# Control_HAT_v0_3A.net
KiCad netlist of a schematic drawn in EAGLE
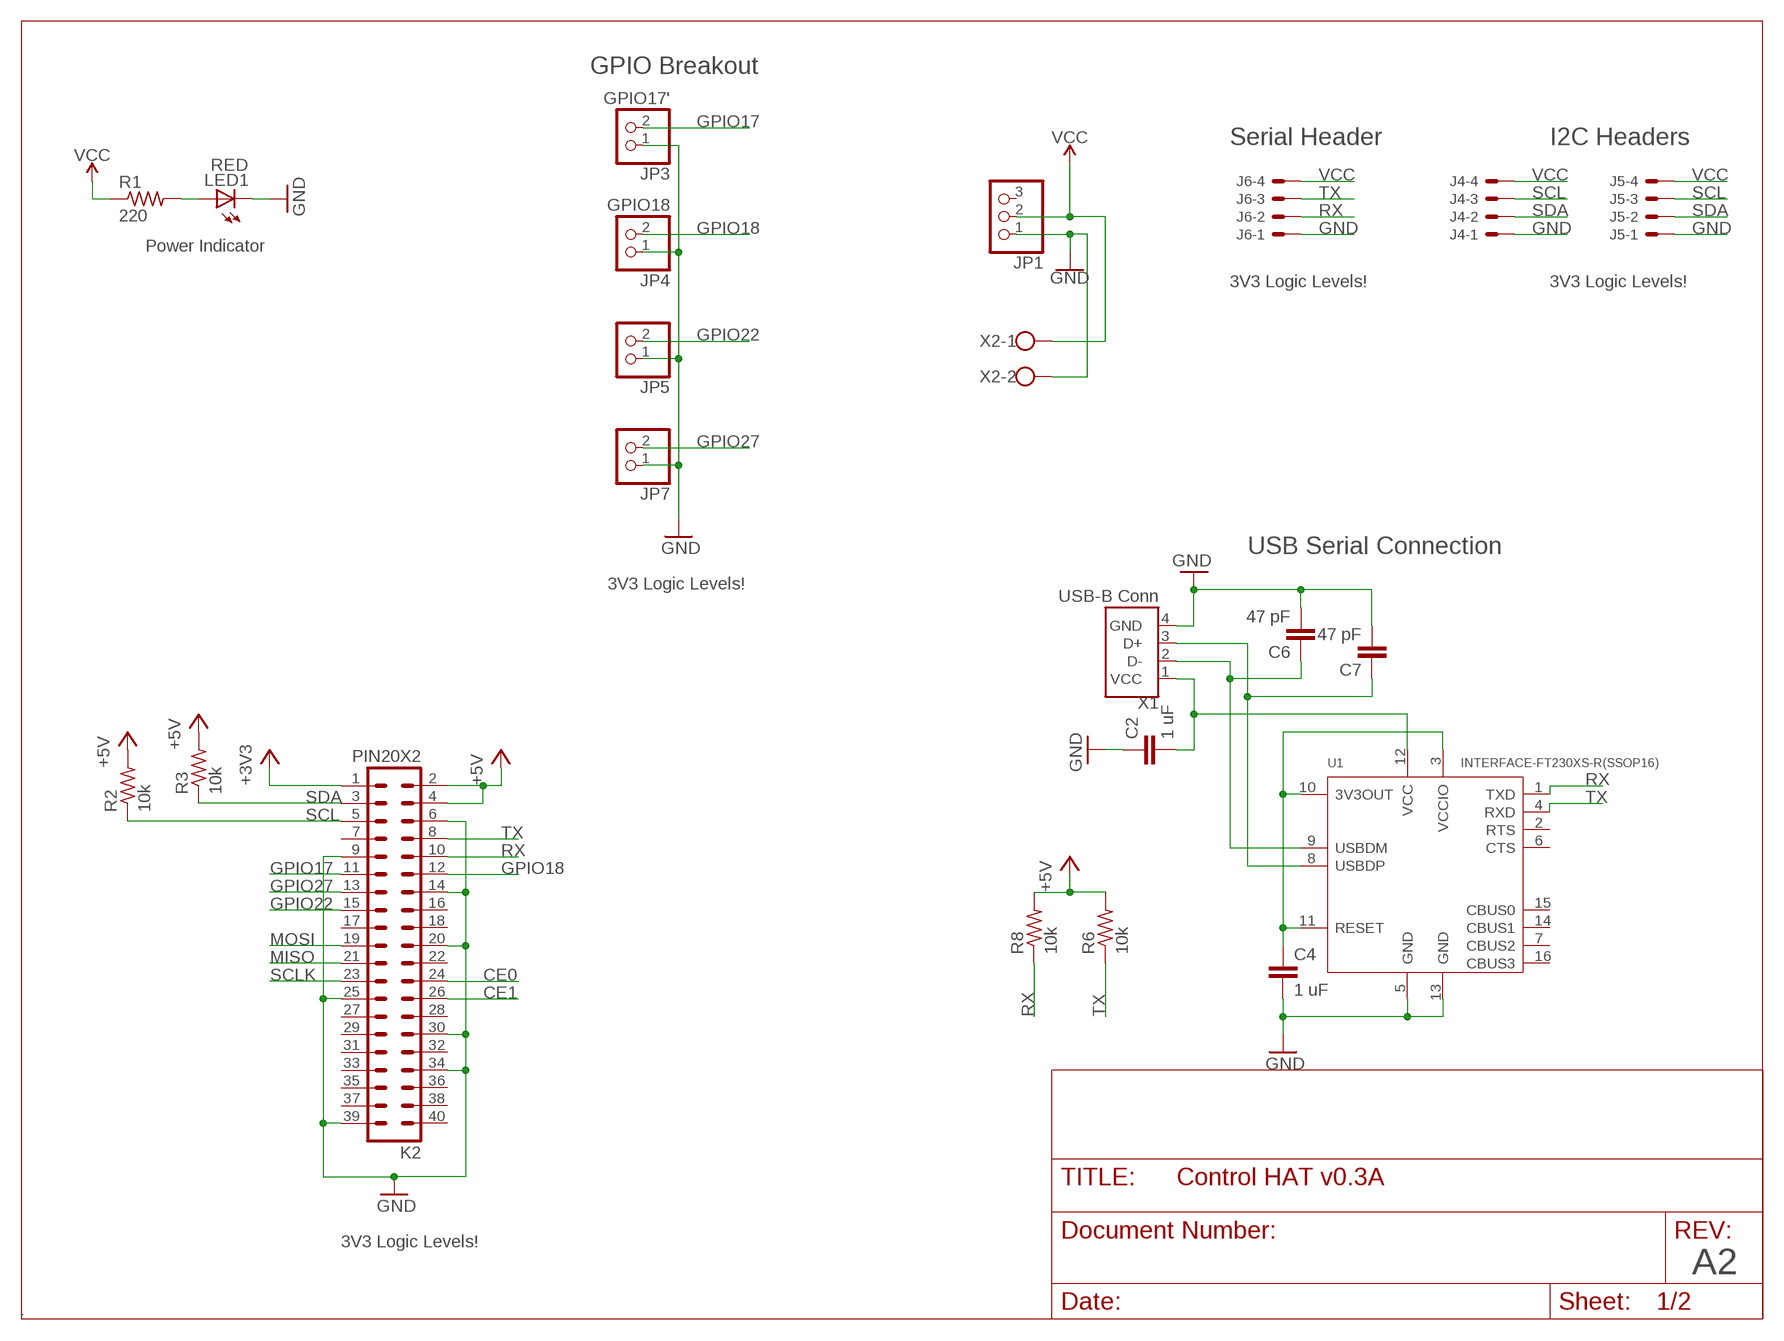
[diagram p0: schematic, sheet 1]
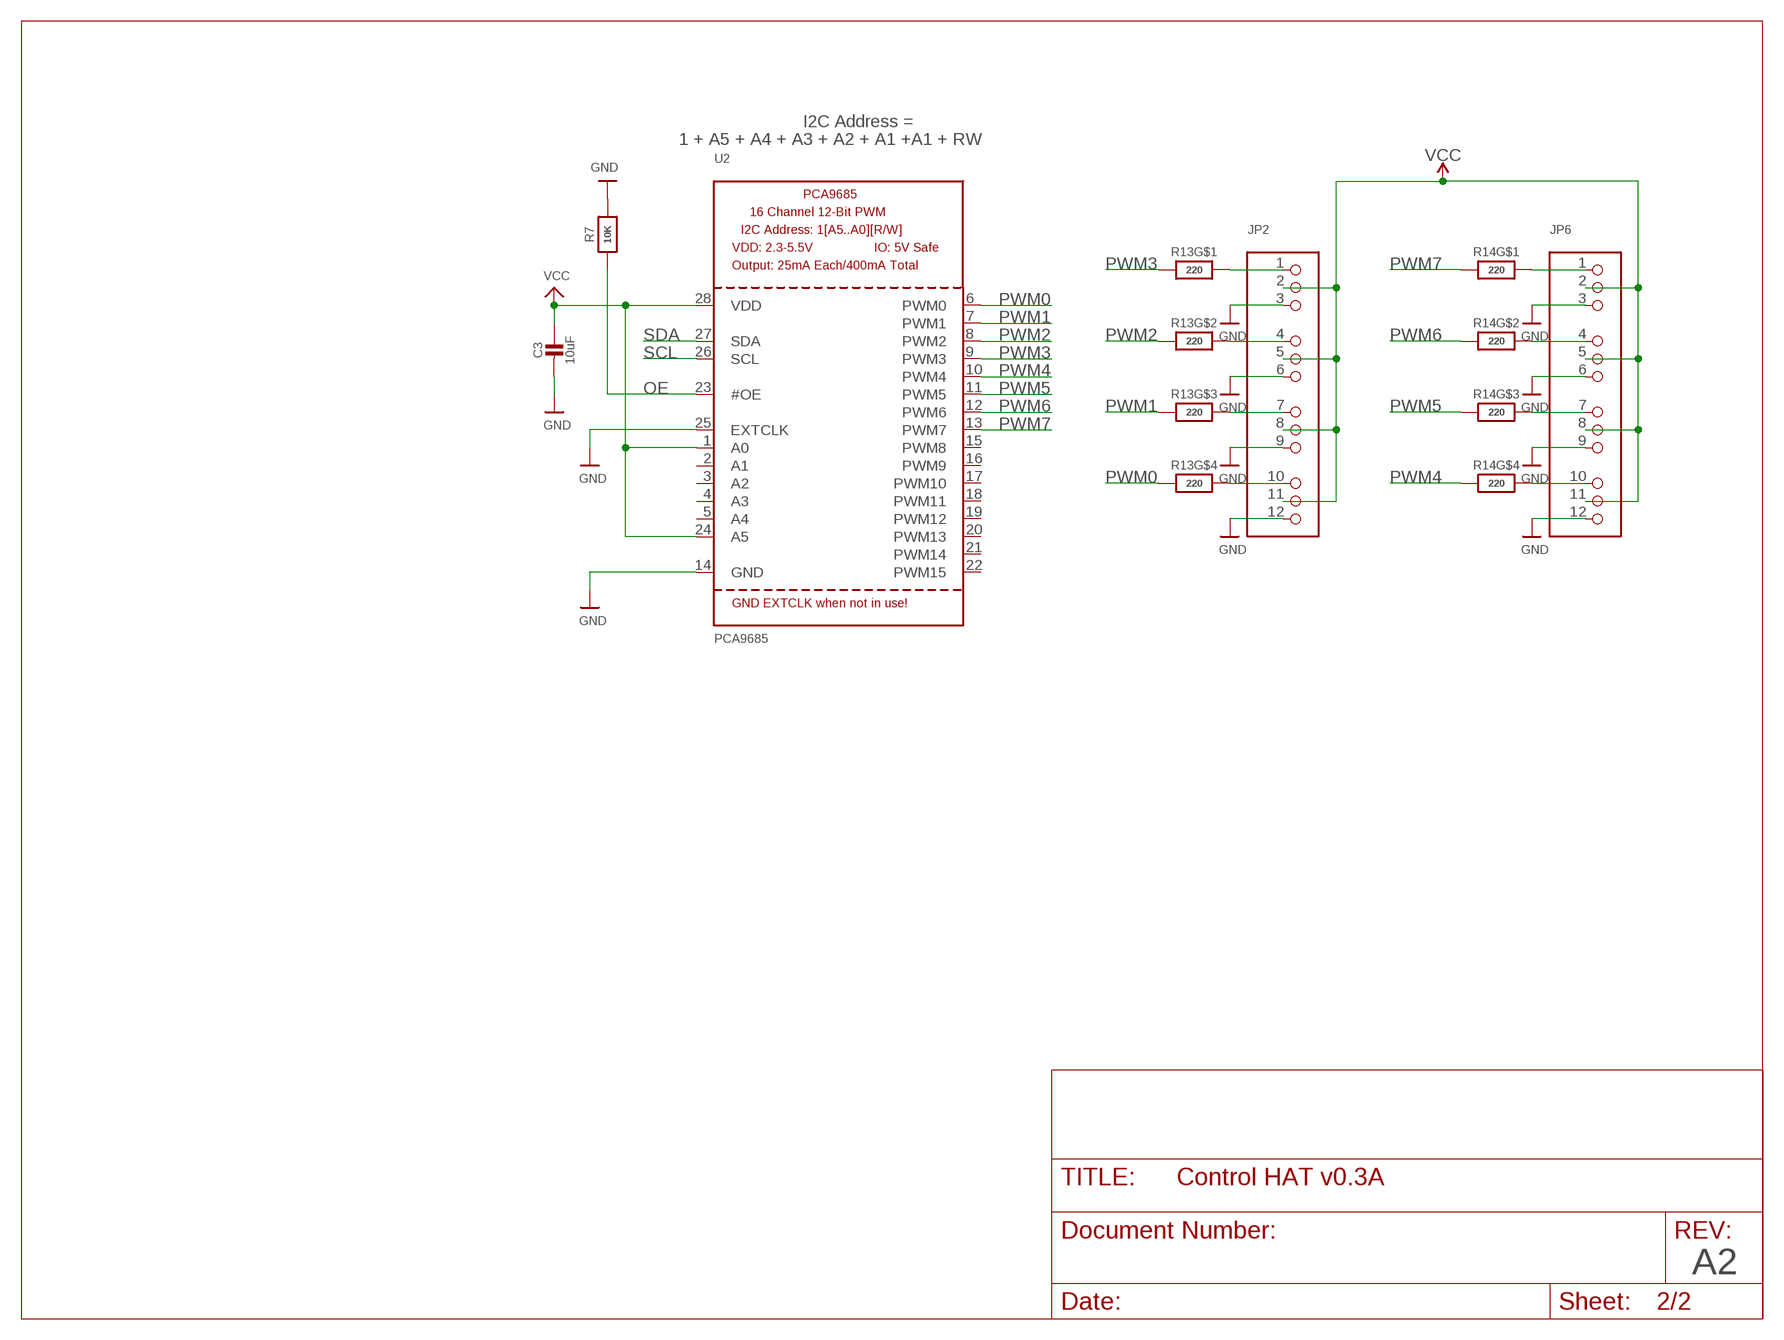
[diagram p1: schematic, sheet 2]

(export (version "E")
  (design (tool "Eeschema 10.0.6"))
  (components
    (comp (ref "C3")
      (value "10uF")
      (footprint "eagle-import:0805-NO")
      (libsource (lib "eagle-import") (part "CAP_CERAMIC0805-NOOUTLINE"))
    )
    (comp (ref "JP2")
      (value "HEADER-3X04")
      (footprint "eagle-import:3X04")
      (libsource (lib "eagle-import") (part "HEADER-3X04"))
    )
    (comp (ref "JP6")
      (value "HEADER-3X04")
      (footprint "eagle-import:3X04")
      (libsource (lib "eagle-import") (part "HEADER-3X04"))
    )
    (comp (ref "R7")
      (value "10K")
      (footprint "eagle-import:0805-NO")
      (libsource (lib "eagle-import") (part "RESISTOR0805_NOOUTLINE"))
    )
    (comp (ref "R13")
      (value "220")
      (footprint "eagle-import:RESPACK_4X0603")
      (libsource (lib "eagle-import") (part "RESISTOR_4PACK"))
    )
    (comp (ref "R14")
      (value "220")
      (footprint "eagle-import:RESPACK_4X0603")
      (libsource (lib "eagle-import") (part "RESISTOR_4PACK"))
    )
    (comp (ref "U2")
      (value "PCA9685")
      (footprint "eagle-import:TSSOP28")
      (libsource (lib "eagle-import") (part "PCA9685"))
    )
    (comp (ref "C2")
      (value "1 uF")
      (footprint "eagle-import:C0603")
      (libsource (lib "eagle-import") (part "C-EUC0603"))
    )
    (comp (ref "C4")
      (value "1 uF")
      (footprint "eagle-import:C0603")
      (libsource (lib "eagle-import") (part "C-EUC0603"))
    )
    (comp (ref "C6")
      (value "47 pF")
      (footprint "eagle-import:C0603")
      (libsource (lib "eagle-import") (part "C-EUC0603"))
    )
    (comp (ref "C7")
      (value "47 pF")
      (footprint "eagle-import:C0603")
      (libsource (lib "eagle-import") (part "C-EUC0603"))
    )
    (comp (ref "J4")
      (value "JST-XH-04-PIN-LONG-PAD")
      (footprint "eagle-import:JST-XH-04-PACKAGE-LONG-PAD")
      (libsource (lib "eagle-import") (part "JST-XH-04-PIN-LONG-PAD"))
    )
    (comp (ref "J5")
      (value "JST-XH-04-PIN-LONG-PAD")
      (footprint "eagle-import:JST-XH-04-PACKAGE-LONG-PAD")
      (libsource (lib "eagle-import") (part "JST-XH-04-PIN-LONG-PAD"))
    )
    (comp (ref "J6")
      (value "JST-XH-04-PIN-LONG-PAD")
      (footprint "eagle-import:JST-XH-04-PACKAGE-LONG-PAD")
      (libsource (lib "eagle-import") (part "JST-XH-04-PIN-LONG-PAD"))
    )
    (comp (ref "JP1")
      (value "PINHD-1X3")
      (footprint "eagle-import:1X03")
      (libsource (lib "eagle-import") (part "PINHD-1X3"))
    )
    (comp (ref "JP3")
      (value "GPIO17'")
      (footprint "eagle-import:1X02")
      (libsource (lib "eagle-import") (part "PINHD-1X2"))
    )
    (comp (ref "JP4")
      (value "GPIO18")
      (footprint "eagle-import:1X02")
      (libsource (lib "eagle-import") (part "PINHD-1X2"))
    )
    (comp (ref "JP5")
      (value "PINHD-1X2")
      (footprint "eagle-import:1X02")
      (libsource (lib "eagle-import") (part "PINHD-1X2"))
    )
    (comp (ref "JP7")
      (value "PINHD-1X2")
      (footprint "eagle-import:1X02")
      (libsource (lib "eagle-import") (part "PINHD-1X2"))
    )
    (comp (ref "K2")
      (value "PIN20X2")
      (footprint "eagle-import:PIN_20X2")
      (libsource (lib "eagle-import") (part "PIN20X2"))
    )
    (comp (ref "LED1")
      (value "RED")
      (footprint "eagle-import:CHIP-LED0603")
      (libsource (lib "eagle-import") (part "LEDCHIP-LED0603"))
    )
    (comp (ref "R1")
      (value "220")
      (footprint "eagle-import:M1206")
      (libsource (lib "eagle-import") (part "R-US_M1206"))
    )
    (comp (ref "R2")
      (value "10k")
      (footprint "eagle-import:M1206")
      (libsource (lib "eagle-import") (part "R-US_M1206"))
    )
    (comp (ref "R3")
      (value "10k")
      (footprint "eagle-import:M1206")
      (libsource (lib "eagle-import") (part "R-US_M1206"))
    )
    (comp (ref "R6")
      (value "10k")
      (footprint "eagle-import:M1206")
      (libsource (lib "eagle-import") (part "R-US_M1206"))
    )
    (comp (ref "R8")
      (value "10k")
      (footprint "eagle-import:M1206")
      (libsource (lib "eagle-import") (part "R-US_M1206"))
    )
    (comp (ref "U1")
      (value "INTERFACE-FT230XS-R(SSOP16)")
      (footprint "eagle-import:SSOP16-0.635-5X4MM")
      (fields (field (name "MF") "FTDI,") (field (name "MP") "FT230XS-R"))
      (libsource (lib "eagle-import") (part "INTERFACE-FT230XS-R(SSOP16)"))
    )
    (comp (ref "X1")
      (value "USB-B Conn")
      (footprint "eagle-import:OST_USB-B1HSB6")
      (fields (field (name "MF") "On Shore") (field (name "MP") "USB-B1HSB6"))
      (libsource (lib "eagle-import") (part "USB-B1HSB6"))
    )
    (comp (ref "X2")
      (value "W237-102")
      (footprint "eagle-import:W237-102")
      (fields (field (name "MPN") "237-102"))
      (libsource (lib "eagle-import") (part "W237-102"))
    )
  )
  (nets
    (net (code "1") (name "+3V3") (class "Default")
      (node (ref "K2") (pin "1") (pinfunction "1_1") (pintype "passive"))
    )
    (net (code "2") (name "+5V") (class "Default")
      (node (ref "K2") (pin "2") (pinfunction "2_2") (pintype "passive"))
      (node (ref "K2") (pin "4") (pinfunction "4_4") (pintype "passive"))
      (node (ref "R2") (pin "2") (pinfunction "2_2") (pintype "passive"))
      (node (ref "R3") (pin "2") (pinfunction "2_2") (pintype "passive"))
      (node (ref "R6") (pin "2") (pinfunction "2_2") (pintype "passive"))
      (node (ref "R8") (pin "2") (pinfunction "2_2") (pintype "passive"))
    )
    (net (code "3") (name "CE0") (class "Default")
      (node (ref "K2") (pin "24") (pinfunction "24_24") (pintype "passive"))
    )
    (net (code "4") (name "CE1") (class "Default")
      (node (ref "K2") (pin "26") (pinfunction "26_26") (pintype "passive"))
    )
    (net (code "5") (name "GND") (class "Default")
      (node (ref "C2") (pin "1") (pinfunction "1_1") (pintype "passive"))
      (node (ref "C3") (pin "2") (pinfunction "2_2") (pintype "passive"))
      (node (ref "C4") (pin "2") (pinfunction "2_2") (pintype "passive"))
      (node (ref "C6") (pin "2") (pinfunction "2_2") (pintype "passive"))
      (node (ref "C7") (pin "2") (pinfunction "2_2") (pintype "passive"))
      (node (ref "J4") (pin "1") (pinfunction "S_1") (pintype "passive"))
      (node (ref "J5") (pin "1") (pinfunction "S_1") (pintype "passive"))
      (node (ref "J6") (pin "1") (pinfunction "S_1") (pintype "passive"))
      (node (ref "JP1") (pin "1") (pinfunction "1_1") (pintype "passive"))
      (node (ref "JP2") (pin "12") (pinfunction "12_12") (pintype "passive"))
      (node (ref "JP2") (pin "3") (pinfunction "3_3") (pintype "passive"))
      (node (ref "JP2") (pin "6") (pinfunction "6_6") (pintype "passive"))
      (node (ref "JP2") (pin "9") (pinfunction "9_9") (pintype "passive"))
      (node (ref "JP3") (pin "1") (pinfunction "1_1") (pintype "passive"))
      (node (ref "JP4") (pin "1") (pinfunction "1_1") (pintype "passive"))
      (node (ref "JP5") (pin "1") (pinfunction "1_1") (pintype "passive"))
      (node (ref "JP6") (pin "12") (pinfunction "12_12") (pintype "passive"))
      (node (ref "JP6") (pin "3") (pinfunction "3_3") (pintype "passive"))
      (node (ref "JP6") (pin "6") (pinfunction "6_6") (pintype "passive"))
      (node (ref "JP6") (pin "9") (pinfunction "9_9") (pintype "passive"))
      (node (ref "JP7") (pin "1") (pinfunction "1_1") (pintype "passive"))
      (node (ref "K2") (pin "14") (pinfunction "14_14") (pintype "passive"))
      (node (ref "K2") (pin "20") (pinfunction "20_20") (pintype "passive"))
      (node (ref "K2") (pin "25") (pinfunction "25_25") (pintype "passive"))
      (node (ref "K2") (pin "30") (pinfunction "30_30") (pintype "passive"))
      (node (ref "K2") (pin "34") (pinfunction "34_34") (pintype "passive"))
      (node (ref "K2") (pin "39") (pinfunction "39_39") (pintype "passive"))
      (node (ref "K2") (pin "6") (pinfunction "6_6") (pintype "passive"))
      (node (ref "K2") (pin "9") (pinfunction "9_9") (pintype "passive"))
      (node (ref "LED1") (pin "C") (pinfunction "C_C") (pintype "passive"))
      (node (ref "R7") (pin "2") (pinfunction "2_2") (pintype "passive"))
      (node (ref "U1") (pin "13") (pinfunction "GND_13") (pintype "bidirectional"))
      (node (ref "U1") (pin "5") (pinfunction "GND_5") (pintype "bidirectional"))
      (node (ref "U2") (pin "14") (pinfunction "GND_14") (pintype "power_in"))
      (node (ref "U2") (pin "25") (pinfunction "EXTCLK_25") (pintype "input"))
      (node (ref "X1") (pin "4") (pinfunction "GND_4") (pintype "power_in"))
      (node (ref "X2") (pin "2") (pinfunction "KL_2") (pintype "passive"))
    )
    (net (code "6") (name "GPIO17") (class "Default")
      (node (ref "JP3") (pin "2") (pinfunction "2_2") (pintype "passive"))
      (node (ref "K2") (pin "11") (pinfunction "11_11") (pintype "passive"))
    )
    (net (code "7") (name "GPIO18") (class "Default")
      (node (ref "JP4") (pin "2") (pinfunction "2_2") (pintype "passive"))
      (node (ref "K2") (pin "12") (pinfunction "12_12") (pintype "passive"))
    )
    (net (code "8") (name "GPIO22") (class "Default")
      (node (ref "JP5") (pin "2") (pinfunction "2_2") (pintype "passive"))
      (node (ref "K2") (pin "15") (pinfunction "15_15") (pintype "passive"))
    )
    (net (code "9") (name "GPIO27") (class "Default")
      (node (ref "JP7") (pin "2") (pinfunction "2_2") (pintype "passive"))
      (node (ref "K2") (pin "13") (pinfunction "13_13") (pintype "passive"))
    )
    (net (code "10") (name "MISO") (class "Default")
      (node (ref "K2") (pin "21") (pinfunction "21_21") (pintype "passive"))
    )
    (net (code "11") (name "MOSI") (class "Default")
      (node (ref "K2") (pin "19") (pinfunction "19_19") (pintype "passive"))
    )
    (net (code "12") (name "Net-(LED1-PadA)") (class "Default")
      (node (ref "LED1") (pin "A") (pinfunction "A_A") (pintype "passive"))
      (node (ref "R1") (pin "2") (pinfunction "2_2") (pintype "passive"))
    )
    (net (code "13") (name "Net-(R13A-2)") (class "Default")
      (node (ref "JP2") (pin "1") (pinfunction "1_1") (pintype "passive"))
      (node (ref "R13") (pin "8") (pinfunction "2_8") (pintype "passive"))
    )
    (net (code "14") (name "Net-(R13B-2)") (class "Default")
      (node (ref "JP2") (pin "4") (pinfunction "4_4") (pintype "passive"))
      (node (ref "R13") (pin "7") (pinfunction "2_7") (pintype "passive"))
    )
    (net (code "15") (name "Net-(R13C-2)") (class "Default")
      (node (ref "JP2") (pin "7") (pinfunction "7_7") (pintype "passive"))
      (node (ref "R13") (pin "6") (pinfunction "2_6") (pintype "passive"))
    )
    (net (code "16") (name "Net-(R13D-2)") (class "Default")
      (node (ref "JP2") (pin "10") (pinfunction "10_10") (pintype "passive"))
      (node (ref "R13") (pin "5") (pinfunction "2_5") (pintype "passive"))
    )
    (net (code "17") (name "Net-(R14A-2)") (class "Default")
      (node (ref "JP6") (pin "1") (pinfunction "1_1") (pintype "passive"))
      (node (ref "R14") (pin "8") (pinfunction "2_8") (pintype "passive"))
    )
    (net (code "18") (name "Net-(R14B-2)") (class "Default")
      (node (ref "JP6") (pin "4") (pinfunction "4_4") (pintype "passive"))
      (node (ref "R14") (pin "7") (pinfunction "2_7") (pintype "passive"))
    )
    (net (code "19") (name "Net-(R14C-2)") (class "Default")
      (node (ref "JP6") (pin "7") (pinfunction "7_7") (pintype "passive"))
      (node (ref "R14") (pin "6") (pinfunction "2_6") (pintype "passive"))
    )
    (net (code "20") (name "Net-(R14D-2)") (class "Default")
      (node (ref "JP6") (pin "10") (pinfunction "10_10") (pintype "passive"))
      (node (ref "R14") (pin "5") (pinfunction "2_5") (pintype "passive"))
    )
    (net (code "21") (name "Net-(U1-3V3OUT)") (class "Default")
      (node (ref "C4") (pin "1") (pinfunction "1_1") (pintype "passive"))
      (node (ref "U1") (pin "10") (pinfunction "3V3OUT_10") (pintype "bidirectional"))
      (node (ref "U1") (pin "11") (pinfunction "RESET_11") (pintype "bidirectional"))
      (node (ref "U1") (pin "3") (pinfunction "VCCIO_3") (pintype "bidirectional"))
    )
    (net (code "22") (name "Net-(U1-USBDM)") (class "Default")
      (node (ref "C6") (pin "1") (pinfunction "1_1") (pintype "passive"))
      (node (ref "U1") (pin "9") (pinfunction "USBDM_9") (pintype "bidirectional"))
      (node (ref "X1") (pin "2") (pinfunction "D-_2") (pintype "bidirectional"))
    )
    (net (code "23") (name "Net-(U1-USBDP)") (class "Default")
      (node (ref "C7") (pin "1") (pinfunction "1_1") (pintype "passive"))
      (node (ref "U1") (pin "8") (pinfunction "USBDP_8") (pintype "bidirectional"))
      (node (ref "X1") (pin "3") (pinfunction "D+_3") (pintype "bidirectional"))
    )
    (net (code "24") (name "Net-(U1-VCC)") (class "Default")
      (node (ref "C2") (pin "2") (pinfunction "2_2") (pintype "passive"))
      (node (ref "U1") (pin "12") (pinfunction "VCC_12") (pintype "bidirectional"))
      (node (ref "X1") (pin "1") (pinfunction "VCC_1") (pintype "power_in"))
    )
    (net (code "25") (name "OE") (class "Default")
      (node (ref "R7") (pin "1") (pinfunction "1_1") (pintype "passive"))
      (node (ref "U2") (pin "23") (pinfunction "#OE_23") (pintype "input"))
    )
    (net (code "26") (name "PWM0") (class "Default")
      (node (ref "R13") (pin "4") (pinfunction "1_4") (pintype "passive"))
      (node (ref "U2") (pin "6") (pinfunction "PWM0_6") (pintype "output"))
    )
    (net (code "27") (name "PWM1") (class "Default")
      (node (ref "R13") (pin "3") (pinfunction "1_3") (pintype "passive"))
      (node (ref "U2") (pin "7") (pinfunction "PWM1_7") (pintype "output"))
    )
    (net (code "28") (name "PWM2") (class "Default")
      (node (ref "R13") (pin "2") (pinfunction "1_2") (pintype "passive"))
      (node (ref "U2") (pin "8") (pinfunction "PWM2_8") (pintype "output"))
    )
    (net (code "29") (name "PWM3") (class "Default")
      (node (ref "R13") (pin "1") (pinfunction "1_1") (pintype "passive"))
      (node (ref "U2") (pin "9") (pinfunction "PWM3_9") (pintype "output"))
    )
    (net (code "30") (name "PWM4") (class "Default")
      (node (ref "R14") (pin "4") (pinfunction "1_4") (pintype "passive"))
      (node (ref "U2") (pin "10") (pinfunction "PWM4_10") (pintype "output"))
    )
    (net (code "31") (name "PWM5") (class "Default")
      (node (ref "R14") (pin "3") (pinfunction "1_3") (pintype "passive"))
      (node (ref "U2") (pin "11") (pinfunction "PWM5_11") (pintype "output"))
    )
    (net (code "32") (name "PWM6") (class "Default")
      (node (ref "R14") (pin "2") (pinfunction "1_2") (pintype "passive"))
      (node (ref "U2") (pin "12") (pinfunction "PWM6_12") (pintype "output"))
    )
    (net (code "33") (name "PWM7") (class "Default")
      (node (ref "R14") (pin "1") (pinfunction "1_1") (pintype "passive"))
      (node (ref "U2") (pin "13") (pinfunction "PWM7_13") (pintype "output"))
    )
    (net (code "34") (name "RX") (class "Default")
      (node (ref "J6") (pin "2") (pinfunction "S_2") (pintype "passive"))
      (node (ref "K2") (pin "10") (pinfunction "10_10") (pintype "passive"))
      (node (ref "R8") (pin "1") (pinfunction "1_1") (pintype "passive"))
      (node (ref "U1") (pin "1") (pinfunction "TXD_1") (pintype "bidirectional"))
    )
    (net (code "35") (name "SCL") (class "Default")
      (node (ref "J4") (pin "3") (pinfunction "S_3") (pintype "passive"))
      (node (ref "J5") (pin "3") (pinfunction "S_3") (pintype "passive"))
      (node (ref "K2") (pin "5") (pinfunction "5_5") (pintype "passive"))
      (node (ref "R2") (pin "1") (pinfunction "1_1") (pintype "passive"))
      (node (ref "U2") (pin "26") (pinfunction "SCL_26") (pintype "bidirectional"))
    )
    (net (code "36") (name "SCLK") (class "Default")
      (node (ref "K2") (pin "23") (pinfunction "23_23") (pintype "passive"))
    )
    (net (code "37") (name "SDA") (class "Default")
      (node (ref "J4") (pin "2") (pinfunction "S_2") (pintype "passive"))
      (node (ref "J5") (pin "2") (pinfunction "S_2") (pintype "passive"))
      (node (ref "K2") (pin "3") (pinfunction "3_3") (pintype "passive"))
      (node (ref "R3") (pin "1") (pinfunction "1_1") (pintype "passive"))
      (node (ref "U2") (pin "27") (pinfunction "SDA_27") (pintype "bidirectional"))
    )
    (net (code "38") (name "TX") (class "Default")
      (node (ref "J6") (pin "3") (pinfunction "S_3") (pintype "passive"))
      (node (ref "K2") (pin "8") (pinfunction "8_8") (pintype "passive"))
      (node (ref "R6") (pin "1") (pinfunction "1_1") (pintype "passive"))
      (node (ref "U1") (pin "4") (pinfunction "RXD_4") (pintype "bidirectional"))
    )
    (net (code "39") (name "VCC") (class "Default")
      (node (ref "C3") (pin "1") (pinfunction "1_1") (pintype "passive"))
      (node (ref "J4") (pin "4") (pinfunction "S_4") (pintype "passive"))
      (node (ref "J5") (pin "4") (pinfunction "S_4") (pintype "passive"))
      (node (ref "J6") (pin "4") (pinfunction "S_4") (pintype "passive"))
      (node (ref "JP1") (pin "2") (pinfunction "2_2") (pintype "passive"))
      (node (ref "JP2") (pin "11") (pinfunction "11_11") (pintype "passive"))
      (node (ref "JP2") (pin "2") (pinfunction "2_2") (pintype "passive"))
      (node (ref "JP2") (pin "5") (pinfunction "5_5") (pintype "passive"))
      (node (ref "JP2") (pin "8") (pinfunction "8_8") (pintype "passive"))
      (node (ref "JP6") (pin "11") (pinfunction "11_11") (pintype "passive"))
      (node (ref "JP6") (pin "2") (pinfunction "2_2") (pintype "passive"))
      (node (ref "JP6") (pin "5") (pinfunction "5_5") (pintype "passive"))
      (node (ref "JP6") (pin "8") (pinfunction "8_8") (pintype "passive"))
      (node (ref "R1") (pin "1") (pinfunction "1_1") (pintype "passive"))
      (node (ref "U2") (pin "1") (pinfunction "A0_1") (pintype "bidirectional"))
      (node (ref "U2") (pin "24") (pinfunction "A5_24") (pintype "bidirectional"))
      (node (ref "U2") (pin "28") (pinfunction "VDD_28") (pintype "power_in"))
      (node (ref "X2") (pin "1") (pinfunction "KL_1") (pintype "passive"))
    )
    (net (code "40") (name "unconnected-(JP1-Pad3)") (class "Default")
      (node (ref "JP1") (pin "3") (pinfunction "3_3") (pintype "passive"))
    )
    (net (code "41") (name "unconnected-(K2-Pad7)") (class "Default")
      (node (ref "K2") (pin "7") (pinfunction "7_7") (pintype "passive"))
    )
    (net (code "42") (name "unconnected-(K2-Pad16)") (class "Default")
      (node (ref "K2") (pin "16") (pinfunction "16_16") (pintype "passive"))
    )
    (net (code "43") (name "unconnected-(K2-Pad17)") (class "Default")
      (node (ref "K2") (pin "17") (pinfunction "17_17") (pintype "passive"))
    )
    (net (code "44") (name "unconnected-(K2-Pad18)") (class "Default")
      (node (ref "K2") (pin "18") (pinfunction "18_18") (pintype "passive"))
    )
    (net (code "45") (name "unconnected-(K2-Pad22)") (class "Default")
      (node (ref "K2") (pin "22") (pinfunction "22_22") (pintype "passive"))
    )
    (net (code "46") (name "unconnected-(K2-Pad27)") (class "Default")
      (node (ref "K2") (pin "27") (pinfunction "27_27") (pintype "passive"))
    )
    (net (code "47") (name "unconnected-(K2-Pad28)") (class "Default")
      (node (ref "K2") (pin "28") (pinfunction "28_28") (pintype "passive"))
    )
    (net (code "48") (name "unconnected-(K2-Pad29)") (class "Default")
      (node (ref "K2") (pin "29") (pinfunction "29_29") (pintype "passive"))
    )
    (net (code "49") (name "unconnected-(K2-Pad31)") (class "Default")
      (node (ref "K2") (pin "31") (pinfunction "31_31") (pintype "passive"))
    )
    (net (code "50") (name "unconnected-(K2-Pad32)") (class "Default")
      (node (ref "K2") (pin "32") (pinfunction "32_32") (pintype "passive"))
    )
    (net (code "51") (name "unconnected-(K2-Pad33)") (class "Default")
      (node (ref "K2") (pin "33") (pinfunction "33_33") (pintype "passive"))
    )
    (net (code "52") (name "unconnected-(K2-Pad35)") (class "Default")
      (node (ref "K2") (pin "35") (pinfunction "35_35") (pintype "passive"))
    )
    (net (code "53") (name "unconnected-(K2-Pad36)") (class "Default")
      (node (ref "K2") (pin "36") (pinfunction "36_36") (pintype "passive"))
    )
    (net (code "54") (name "unconnected-(K2-Pad37)") (class "Default")
      (node (ref "K2") (pin "37") (pinfunction "37_37") (pintype "passive"))
    )
    (net (code "55") (name "unconnected-(K2-Pad38)") (class "Default")
      (node (ref "K2") (pin "38") (pinfunction "38_38") (pintype "passive"))
    )
    (net (code "56") (name "unconnected-(K2-Pad40)") (class "Default")
      (node (ref "K2") (pin "40") (pinfunction "40_40") (pintype "passive"))
    )
    (net (code "57") (name "unconnected-(U1-CBUS0-Pad15)") (class "Default")
      (node (ref "U1") (pin "15") (pinfunction "CBUS0_15") (pintype "bidirectional"))
    )
    (net (code "58") (name "unconnected-(U1-CBUS1-Pad14)") (class "Default")
      (node (ref "U1") (pin "14") (pinfunction "CBUS1_14") (pintype "bidirectional"))
    )
    (net (code "59") (name "unconnected-(U1-CBUS2-Pad7)") (class "Default")
      (node (ref "U1") (pin "7") (pinfunction "CBUS2_7") (pintype "bidirectional"))
    )
    (net (code "60") (name "unconnected-(U1-CBUS3-Pad16)") (class "Default")
      (node (ref "U1") (pin "16") (pinfunction "CBUS3_16") (pintype "bidirectional"))
    )
    (net (code "61") (name "unconnected-(U1-CTS-Pad6)") (class "Default")
      (node (ref "U1") (pin "6") (pinfunction "CTS_6") (pintype "bidirectional"))
    )
    (net (code "62") (name "unconnected-(U1-RTS-Pad2)") (class "Default")
      (node (ref "U1") (pin "2") (pinfunction "RTS_2") (pintype "bidirectional"))
    )
    (net (code "63") (name "unconnected-(U2-A1-Pad2)") (class "Default")
      (node (ref "U2") (pin "2") (pinfunction "A1_2") (pintype "bidirectional"))
    )
    (net (code "64") (name "unconnected-(U2-A2-Pad3)") (class "Default")
      (node (ref "U2") (pin "3") (pinfunction "A2_3") (pintype "bidirectional"))
    )
    (net (code "65") (name "unconnected-(U2-A3-Pad4)") (class "Default")
      (node (ref "U2") (pin "4") (pinfunction "A3_4") (pintype "bidirectional"))
    )
    (net (code "66") (name "unconnected-(U2-A4-Pad5)") (class "Default")
      (node (ref "U2") (pin "5") (pinfunction "A4_5") (pintype "bidirectional"))
    )
    (net (code "67") (name "unconnected-(U2-PWM8-Pad15)") (class "Default")
      (node (ref "U2") (pin "15") (pinfunction "PWM8_15") (pintype "output"))
    )
    (net (code "68") (name "unconnected-(U2-PWM9-Pad16)") (class "Default")
      (node (ref "U2") (pin "16") (pinfunction "PWM9_16") (pintype "output"))
    )
    (net (code "69") (name "unconnected-(U2-PWM10-Pad17)") (class "Default")
      (node (ref "U2") (pin "17") (pinfunction "PWM10_17") (pintype "output"))
    )
    (net (code "70") (name "unconnected-(U2-PWM11-Pad18)") (class "Default")
      (node (ref "U2") (pin "18") (pinfunction "PWM11_18") (pintype "output"))
    )
    (net (code "71") (name "unconnected-(U2-PWM12-Pad19)") (class "Default")
      (node (ref "U2") (pin "19") (pinfunction "PWM12_19") (pintype "output"))
    )
    (net (code "72") (name "unconnected-(U2-PWM13-Pad20)") (class "Default")
      (node (ref "U2") (pin "20") (pinfunction "PWM13_20") (pintype "output"))
    )
    (net (code "73") (name "unconnected-(U2-PWM14-Pad21)") (class "Default")
      (node (ref "U2") (pin "21") (pinfunction "PWM14_21") (pintype "output"))
    )
    (net (code "74") (name "unconnected-(U2-PWM15-Pad22)") (class "Default")
      (node (ref "U2") (pin "22") (pinfunction "PWM15_22") (pintype "output"))
    )
  )
)
